# power.net
KiCad netlist of a schematic drawn in Altium Designer
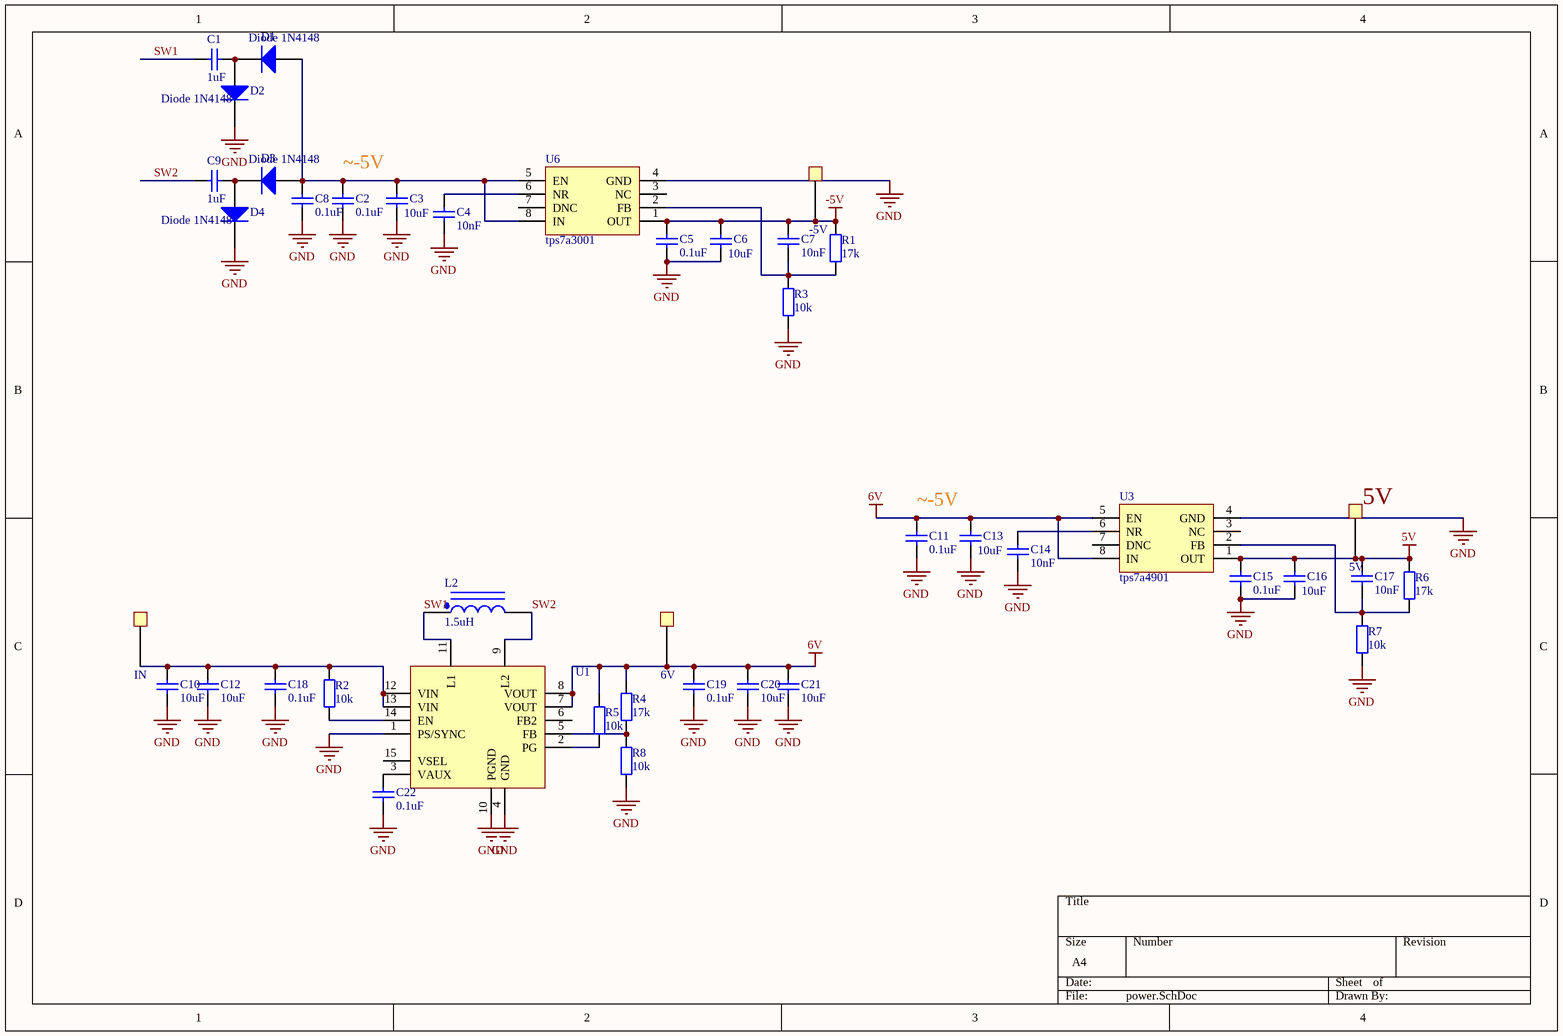
[diagram p0: power.SchDoc]

(export (version "E")
  (design (tool "Eeschema 10.0.6"))
  (components
    (comp (ref "-5V") (value "TestPad") (footprint "TestPad") (libsource (lib "sch") (part "TestPad")))
    (comp (ref "5V") (value "TestPad") (footprint "TestPad") (libsource (lib "sch") (part "TestPad")))
    (comp (ref "6V") (value "TestPad") (footprint "TestPad") (libsource (lib "sch") (part "TestPad")))
    (comp (ref "C1")
      (value "1uF")
      (footprint "0603L")
      (description "Capacitor")
      (fields (field (name "PUBLISHER") "Altium Limited"))
      (libsource (lib "RTC6705") (part "Cap"))
    )
    (comp (ref "C2")
      (value "0.1uF")
      (footprint "0603L")
      (description "Capacitor")
      (fields (field (name "PUBLISHER") "Altium Limited"))
      (libsource (lib "RTC6705") (part "Cap"))
    )
    (comp (ref "C3")
      (value "10uF")
      (footprint "0805")
      (description "Capacitor")
      (fields (field (name "PUBLISHER") "Altium Limited"))
      (libsource (lib "RTC6705") (part "Cap"))
    )
    (comp (ref "C4")
      (value "10nF")
      (footprint "0402")
      (description "Capacitor")
      (fields (field (name "PUBLISHER") "Altium Limited"))
      (libsource (lib "RTC6705") (part "Cap"))
    )
    (comp (ref "C5")
      (value "0.1uF")
      (footprint "0603L")
      (description "Capacitor")
      (fields (field (name "PUBLISHER") "Altium Limited"))
      (libsource (lib "RTC6705") (part "Cap"))
    )
    (comp (ref "C6")
      (value "10uF")
      (footprint "0805")
      (description "Capacitor")
      (fields (field (name "PUBLISHER") "Altium Limited"))
      (libsource (lib "RTC6705") (part "Cap"))
    )
    (comp (ref "C7")
      (value "10nF")
      (footprint "0402")
      (description "Capacitor")
      (fields (field (name "PUBLISHER") "Altium Limited"))
      (libsource (lib "RTC6705") (part "Cap"))
    )
    (comp (ref "C8")
      (value "0.1uF")
      (footprint "0603L")
      (description "Capacitor")
      (fields (field (name "PUBLISHER") "Altium Limited"))
      (libsource (lib "RTC6705") (part "Cap"))
    )
    (comp (ref "C9")
      (value "1uF")
      (footprint "0603L")
      (description "Capacitor")
      (fields (field (name "PUBLISHER") "Altium Limited"))
      (libsource (lib "RTC6705") (part "Cap"))
    )
    (comp (ref "C10")
      (value "10uF")
      (footprint "0805")
      (description "Capacitor")
      (fields (field (name "PUBLISHER") "Altium Limited"))
      (libsource (lib "RTC6705") (part "Cap"))
    )
    (comp (ref "C11")
      (value "0.1uF")
      (footprint "0603L")
      (description "Capacitor")
      (fields (field (name "PUBLISHER") "Altium Limited"))
      (libsource (lib "RTC6705") (part "Cap"))
    )
    (comp (ref "C12")
      (value "10uF")
      (footprint "0805")
      (description "Capacitor")
      (fields (field (name "PUBLISHER") "Altium Limited"))
      (libsource (lib "RTC6705") (part "Cap"))
    )
    (comp (ref "C13")
      (value "10uF")
      (footprint "0805")
      (description "Capacitor")
      (fields (field (name "PUBLISHER") "Altium Limited"))
      (libsource (lib "RTC6705") (part "Cap"))
    )
    (comp (ref "C14")
      (value "10nF")
      (footprint "0402")
      (description "Capacitor")
      (fields (field (name "PUBLISHER") "Altium Limited"))
      (libsource (lib "RTC6705") (part "Cap"))
    )
    (comp (ref "C15")
      (value "0.1uF")
      (footprint "0603L")
      (description "Capacitor")
      (fields (field (name "PUBLISHER") "Altium Limited"))
      (libsource (lib "RTC6705") (part "Cap"))
    )
    (comp (ref "C16")
      (value "10uF")
      (footprint "0805")
      (description "Capacitor")
      (fields (field (name "PUBLISHER") "Altium Limited"))
      (libsource (lib "RTC6705") (part "Cap"))
    )
    (comp (ref "C17")
      (value "10nF")
      (footprint "0402")
      (description "Capacitor")
      (fields (field (name "PUBLISHER") "Altium Limited"))
      (libsource (lib "RTC6705") (part "Cap"))
    )
    (comp (ref "C18")
      (value "0.1uF")
      (footprint "0603L")
      (description "Capacitor")
      (fields (field (name "PUBLISHER") "Altium Limited"))
      (libsource (lib "RTC6705") (part "Cap"))
    )
    (comp (ref "C19")
      (value "0.1uF")
      (footprint "0603L")
      (description "Capacitor")
      (fields (field (name "PUBLISHER") "Altium Limited"))
      (libsource (lib "RTC6705") (part "Cap"))
    )
    (comp (ref "C20")
      (value "10uF")
      (footprint "0805")
      (description "Capacitor")
      (fields (field (name "PUBLISHER") "Altium Limited"))
      (libsource (lib "RTC6705") (part "Cap"))
    )
    (comp (ref "C21")
      (value "10uF")
      (footprint "0805")
      (description "Capacitor")
      (fields (field (name "PUBLISHER") "Altium Limited"))
      (libsource (lib "RTC6705") (part "Cap"))
    )
    (comp (ref "C22")
      (value "0.1uF")
      (footprint "0402")
      (description "Capacitor")
      (fields (field (name "PUBLISHER") "Altium Limited"))
      (libsource (lib "RTC6705") (part "Cap"))
    )
    (comp (ref "D1")
      (value "Diode 1N4148")
      (footprint "LC-SOD-323")
      (description "High Conductance Fast Diode")
      (fields (field (name "PUBLISHER") "Altium Limited"))
      (libsource (lib "Miscellaneous Devices") (part "Diode 1N4148"))
    )
    (comp (ref "D2")
      (value "Diode 1N4148")
      (footprint "LC-SOD-323")
      (description "High Conductance Fast Diode")
      (fields (field (name "PUBLISHER") "Altium Limited"))
      (libsource (lib "Miscellaneous Devices") (part "Diode 1N4148"))
    )
    (comp (ref "D3")
      (value "Diode 1N4148")
      (footprint "LC-SOD-323")
      (description "High Conductance Fast Diode")
      (fields (field (name "PUBLISHER") "Altium Limited"))
      (libsource (lib "Miscellaneous Devices") (part "Diode 1N4148"))
    )
    (comp (ref "D4")
      (value "Diode 1N4148")
      (footprint "LC-SOD-323")
      (description "High Conductance Fast Diode")
      (fields (field (name "PUBLISHER") "Altium Limited"))
      (libsource (lib "Miscellaneous Devices") (part "Diode 1N4148"))
    )
    (comp (ref "IN") (value "TestPad") (footprint "TestPad") (libsource (lib "sch") (part "TestPad")))
    (comp (ref "L2")
      (value "1.5uH")
      (footprint "L4015")
      (description "Magnetic-Core Inductor with Winding Polarity Marking")
      (fields (field (name "PUBLISHER") "Altium Limited"))
      (libsource (lib "Miscellaneous Devices") (part "Inductor Iron Dot"))
    )
    (comp (ref "R1")
      (value "17k")
      (footprint "0402")
      (description "Resistor")
      (fields (field (name "PUBLISHER") "Altium Limited"))
      (libsource (lib "RTC6705") (part "Res2"))
    )
    (comp (ref "R2")
      (value "10k")
      (footprint "0402")
      (description "Resistor")
      (fields (field (name "PUBLISHER") "Altium Limited"))
      (libsource (lib "RTC6705") (part "Res2"))
    )
    (comp (ref "R3")
      (value "10k")
      (footprint "0402")
      (description "Resistor")
      (fields (field (name "PUBLISHER") "Altium Limited"))
      (libsource (lib "RTC6705") (part "Res2"))
    )
    (comp (ref "R4")
      (value "17k")
      (footprint "0402")
      (description "Resistor")
      (fields (field (name "PUBLISHER") "Altium Limited"))
      (libsource (lib "RTC6705") (part "Res2"))
    )
    (comp (ref "R5")
      (value "10k")
      (footprint "0402")
      (description "Resistor")
      (fields (field (name "PUBLISHER") "Altium Limited"))
      (libsource (lib "RTC6705") (part "Res2"))
    )
    (comp (ref "R6")
      (value "17k")
      (footprint "0402")
      (description "Resistor")
      (fields (field (name "PUBLISHER") "Altium Limited"))
      (libsource (lib "RTC6705") (part "Res2"))
    )
    (comp (ref "R7")
      (value "10k")
      (footprint "0402")
      (description "Resistor")
      (fields (field (name "PUBLISHER") "Altium Limited"))
      (libsource (lib "RTC6705") (part "Res2"))
    )
    (comp (ref "R8")
      (value "10k")
      (footprint "0402")
      (description "Resistor")
      (fields (field (name "PUBLISHER") "Altium Limited"))
      (libsource (lib "RTC6705") (part "Res2"))
    )
    (comp (ref "U1") (value "tps63070") (footprint "TPS63070") (libsource (lib "tps63070") (part "tps63070")))
    (comp (ref "U3")
      (value "tps7a4901")
      (footprint "MSOP8/VSSOP8")
      (libsource (lib "F4SDR") (part "tps7a3001"))
    )
    (comp (ref "U6")
      (value "tps7a3001")
      (footprint "MSOP8/VSSOP8")
      (libsource (lib "F4SDR") (part "tps7a3001"))
    )
  )
  (nets
    (net (code "1") (name "-5V") (class "Default")
      (node (ref "-5V") (pin "1") (pinfunction "3_1") (pintype "passive"))
      (node (ref "C5") (pin "1") (pinfunction "1_1") (pintype "passive"))
      (node (ref "C6") (pin "2") (pinfunction "2_2") (pintype "passive"))
      (node (ref "C7") (pin "1") (pinfunction "1_1") (pintype "passive"))
      (node (ref "R1") (pin "2") (pinfunction "2_2") (pintype "passive"))
      (node (ref "U6") (pin "1") (pinfunction "OUT_1") (pintype "passive"))
    )
    (net (code "2") (name "/SW1") (class "Default")
      (node (ref "C1") (pin "2") (pinfunction "2_2") (pintype "passive"))
      (node (ref "L2") (pin "1") (pinfunction "1_1") (pintype "passive"))
      (node (ref "U1") (pin "11") (pinfunction "L1_11") (pintype "passive"))
    )
    (net (code "3") (name "/SW2") (class "Default")
      (node (ref "C9") (pin "2") (pinfunction "2_2") (pintype "passive"))
      (node (ref "L2") (pin "2") (pinfunction "2_2") (pintype "passive"))
      (node (ref "U1") (pin "9") (pinfunction "L2_9") (pintype "passive"))
    )
    (net (code "4") (name "5V") (class "Default")
      (node (ref "5V") (pin "1") (pinfunction "3_1") (pintype "passive"))
      (node (ref "C15") (pin "1") (pinfunction "1_1") (pintype "passive"))
      (node (ref "C16") (pin "2") (pinfunction "2_2") (pintype "passive"))
      (node (ref "C17") (pin "1") (pinfunction "1_1") (pintype "passive"))
      (node (ref "R6") (pin "2") (pinfunction "2_2") (pintype "passive"))
      (node (ref "U3") (pin "1") (pinfunction "OUT_1") (pintype "passive"))
    )
    (net (code "5") (name "6V") (class "Default")
      (node (ref "6V") (pin "1") (pinfunction "3_1") (pintype "passive"))
      (node (ref "C11") (pin "1") (pinfunction "1_1") (pintype "passive"))
      (node (ref "C13") (pin "2") (pinfunction "2_2") (pintype "passive"))
      (node (ref "C19") (pin "2") (pinfunction "2_2") (pintype "passive"))
      (node (ref "C20") (pin "2") (pinfunction "2_2") (pintype "passive"))
      (node (ref "C21") (pin "2") (pinfunction "2_2") (pintype "passive"))
      (node (ref "R4") (pin "2") (pinfunction "2_2") (pintype "passive"))
      (node (ref "R5") (pin "2") (pinfunction "2_2") (pintype "passive"))
      (node (ref "U1") (pin "7") (pinfunction "VOUT_7") (pintype "passive"))
      (node (ref "U1") (pin "8") (pinfunction "VOUT_8") (pintype "passive"))
      (node (ref "U3") (pin "5") (pinfunction "EN_5") (pintype "passive"))
      (node (ref "U3") (pin "8") (pinfunction "IN_8") (pintype "passive"))
    )
    (net (code "6") (name "GND") (class "Default")
      (node (ref "C10") (pin "1") (pinfunction "1_1") (pintype "passive"))
      (node (ref "C11") (pin "2") (pinfunction "2_2") (pintype "passive"))
      (node (ref "C12") (pin "1") (pinfunction "1_1") (pintype "passive"))
      (node (ref "C13") (pin "1") (pinfunction "1_1") (pintype "passive"))
      (node (ref "C14") (pin "2") (pinfunction "2_2") (pintype "passive"))
      (node (ref "C15") (pin "2") (pinfunction "2_2") (pintype "passive"))
      (node (ref "C16") (pin "1") (pinfunction "1_1") (pintype "passive"))
      (node (ref "C18") (pin "1") (pinfunction "1_1") (pintype "passive"))
      (node (ref "C19") (pin "1") (pinfunction "1_1") (pintype "passive"))
      (node (ref "C2") (pin "2") (pinfunction "2_2") (pintype "passive"))
      (node (ref "C20") (pin "1") (pinfunction "1_1") (pintype "passive"))
      (node (ref "C21") (pin "1") (pinfunction "1_1") (pintype "passive"))
      (node (ref "C22") (pin "2") (pinfunction "2_2") (pintype "passive"))
      (node (ref "C3") (pin "1") (pinfunction "1_1") (pintype "passive"))
      (node (ref "C4") (pin "2") (pinfunction "2_2") (pintype "passive"))
      (node (ref "C5") (pin "2") (pinfunction "2_2") (pintype "passive"))
      (node (ref "C6") (pin "1") (pinfunction "1_1") (pintype "passive"))
      (node (ref "C8") (pin "2") (pinfunction "2_2") (pintype "passive"))
      (node (ref "D2") (pin "2") (pinfunction "K_2") (pintype "passive"))
      (node (ref "D4") (pin "2") (pinfunction "K_2") (pintype "passive"))
      (node (ref "R3") (pin "1") (pinfunction "1_1") (pintype "passive"))
      (node (ref "R7") (pin "1") (pinfunction "1_1") (pintype "passive"))
      (node (ref "R8") (pin "1") (pinfunction "1_1") (pintype "passive"))
      (node (ref "U1") (pin "1") (pinfunction "PS/SYNC_1") (pintype "passive"))
      (node (ref "U1") (pin "10") (pinfunction "PGND_10") (pintype "passive"))
      (node (ref "U1") (pin "4") (pinfunction "GND_4") (pintype "passive"))
      (node (ref "U3") (pin "4") (pinfunction "GND_4") (pintype "passive"))
      (node (ref "U6") (pin "4") (pinfunction "GND_4") (pintype "passive"))
    )
    (net (code "7") (name "Net-(D1-A)") (class "Default")
      (node (ref "C2") (pin "1") (pinfunction "1_1") (pintype "passive"))
      (node (ref "C3") (pin "2") (pinfunction "2_2") (pintype "passive"))
      (node (ref "C8") (pin "1") (pinfunction "1_1") (pintype "passive"))
      (node (ref "D1") (pin "1") (pinfunction "A_1") (pintype "passive"))
      (node (ref "D3") (pin "1") (pinfunction "A_1") (pintype "passive"))
      (node (ref "U6") (pin "5") (pinfunction "EN_5") (pintype "passive"))
      (node (ref "U6") (pin "8") (pinfunction "IN_8") (pintype "passive"))
    )
    (net (code "8") (name "Net-(D1-K)") (class "Default")
      (node (ref "C1") (pin "1") (pinfunction "1_1") (pintype "passive"))
      (node (ref "D1") (pin "2") (pinfunction "K_2") (pintype "passive"))
      (node (ref "D2") (pin "1") (pinfunction "A_1") (pintype "passive"))
    )
    (net (code "9") (name "Net-(D3-K)") (class "Default")
      (node (ref "C9") (pin "1") (pinfunction "1_1") (pintype "passive"))
      (node (ref "D3") (pin "2") (pinfunction "K_2") (pintype "passive"))
      (node (ref "D4") (pin "1") (pinfunction "A_1") (pintype "passive"))
    )
    (net (code "10") (name "Net-(IN-3)") (class "Default")
      (node (ref "C10") (pin "2") (pinfunction "2_2") (pintype "passive"))
      (node (ref "C12") (pin "2") (pinfunction "2_2") (pintype "passive"))
      (node (ref "C18") (pin "2") (pinfunction "2_2") (pintype "passive"))
      (node (ref "IN") (pin "1") (pinfunction "3_1") (pintype "passive"))
      (node (ref "R2") (pin "2") (pinfunction "2_2") (pintype "passive"))
      (node (ref "U1") (pin "12") (pinfunction "VIN_12") (pintype "passive"))
      (node (ref "U1") (pin "13") (pinfunction "VIN_13") (pintype "passive"))
    )
    (net (code "11") (name "Net-(U1-EN)") (class "Default")
      (node (ref "R2") (pin "1") (pinfunction "1_1") (pintype "passive"))
      (node (ref "U1") (pin "14") (pinfunction "EN_14") (pintype "passive"))
    )
    (net (code "12") (name "Net-(U1-FB)") (class "Default")
      (node (ref "R4") (pin "1") (pinfunction "1_1") (pintype "passive"))
      (node (ref "R8") (pin "2") (pinfunction "2_2") (pintype "passive"))
      (node (ref "U1") (pin "5") (pinfunction "FB_5") (pintype "passive"))
    )
    (net (code "13") (name "Net-(U1-PG)") (class "Default")
      (node (ref "R5") (pin "1") (pinfunction "1_1") (pintype "passive"))
      (node (ref "U1") (pin "2") (pinfunction "PG_2") (pintype "passive"))
    )
    (net (code "14") (name "Net-(U1-VAUX)") (class "Default")
      (node (ref "C22") (pin "1") (pinfunction "1_1") (pintype "passive"))
      (node (ref "U1") (pin "3") (pinfunction "VAUX_3") (pintype "passive"))
    )
    (net (code "15") (name "Net-(U3-FB)") (class "Default")
      (node (ref "C17") (pin "2") (pinfunction "2_2") (pintype "passive"))
      (node (ref "R6") (pin "1") (pinfunction "1_1") (pintype "passive"))
      (node (ref "R7") (pin "2") (pinfunction "2_2") (pintype "passive"))
      (node (ref "U3") (pin "2") (pinfunction "FB_2") (pintype "passive"))
    )
    (net (code "16") (name "Net-(U3-NR)") (class "Default")
      (node (ref "C14") (pin "1") (pinfunction "1_1") (pintype "passive"))
      (node (ref "U3") (pin "6") (pinfunction "NR_6") (pintype "passive"))
    )
    (net (code "17") (name "Net-(U6-FB)") (class "Default")
      (node (ref "C7") (pin "2") (pinfunction "2_2") (pintype "passive"))
      (node (ref "R1") (pin "1") (pinfunction "1_1") (pintype "passive"))
      (node (ref "R3") (pin "2") (pinfunction "2_2") (pintype "passive"))
      (node (ref "U6") (pin "2") (pinfunction "FB_2") (pintype "passive"))
    )
    (net (code "18") (name "Net-(U6-NR)") (class "Default")
      (node (ref "C4") (pin "1") (pinfunction "1_1") (pintype "passive"))
      (node (ref "U6") (pin "6") (pinfunction "NR_6") (pintype "passive"))
    )
    (net (code "19") (name "unconnected-(U1-FB2-Pad6)") (class "Default")
      (node (ref "U1") (pin "6") (pinfunction "FB2_6") (pintype "passive"))
    )
    (net (code "20") (name "unconnected-(U1-VSEL-Pad15)") (class "Default")
      (node (ref "U1") (pin "15") (pinfunction "VSEL_15") (pintype "passive"))
    )
    (net (code "21") (name "unconnected-(U3-DNC-Pad7)") (class "Default")
      (node (ref "U3") (pin "7") (pinfunction "DNC_7") (pintype "passive"))
    )
    (net (code "22") (name "unconnected-(U3-NC-Pad3)") (class "Default")
      (node (ref "U3") (pin "3") (pinfunction "NC_3") (pintype "passive"))
    )
    (net (code "23") (name "unconnected-(U6-DNC-Pad7)") (class "Default")
      (node (ref "U6") (pin "7") (pinfunction "DNC_7") (pintype "passive"))
    )
    (net (code "24") (name "unconnected-(U6-NC-Pad3)") (class "Default")
      (node (ref "U6") (pin "3") (pinfunction "NC_3") (pintype "passive"))
    )
  )
)
